# Schematic.net
KiCad netlist of a schematic drawn in Altium Designer
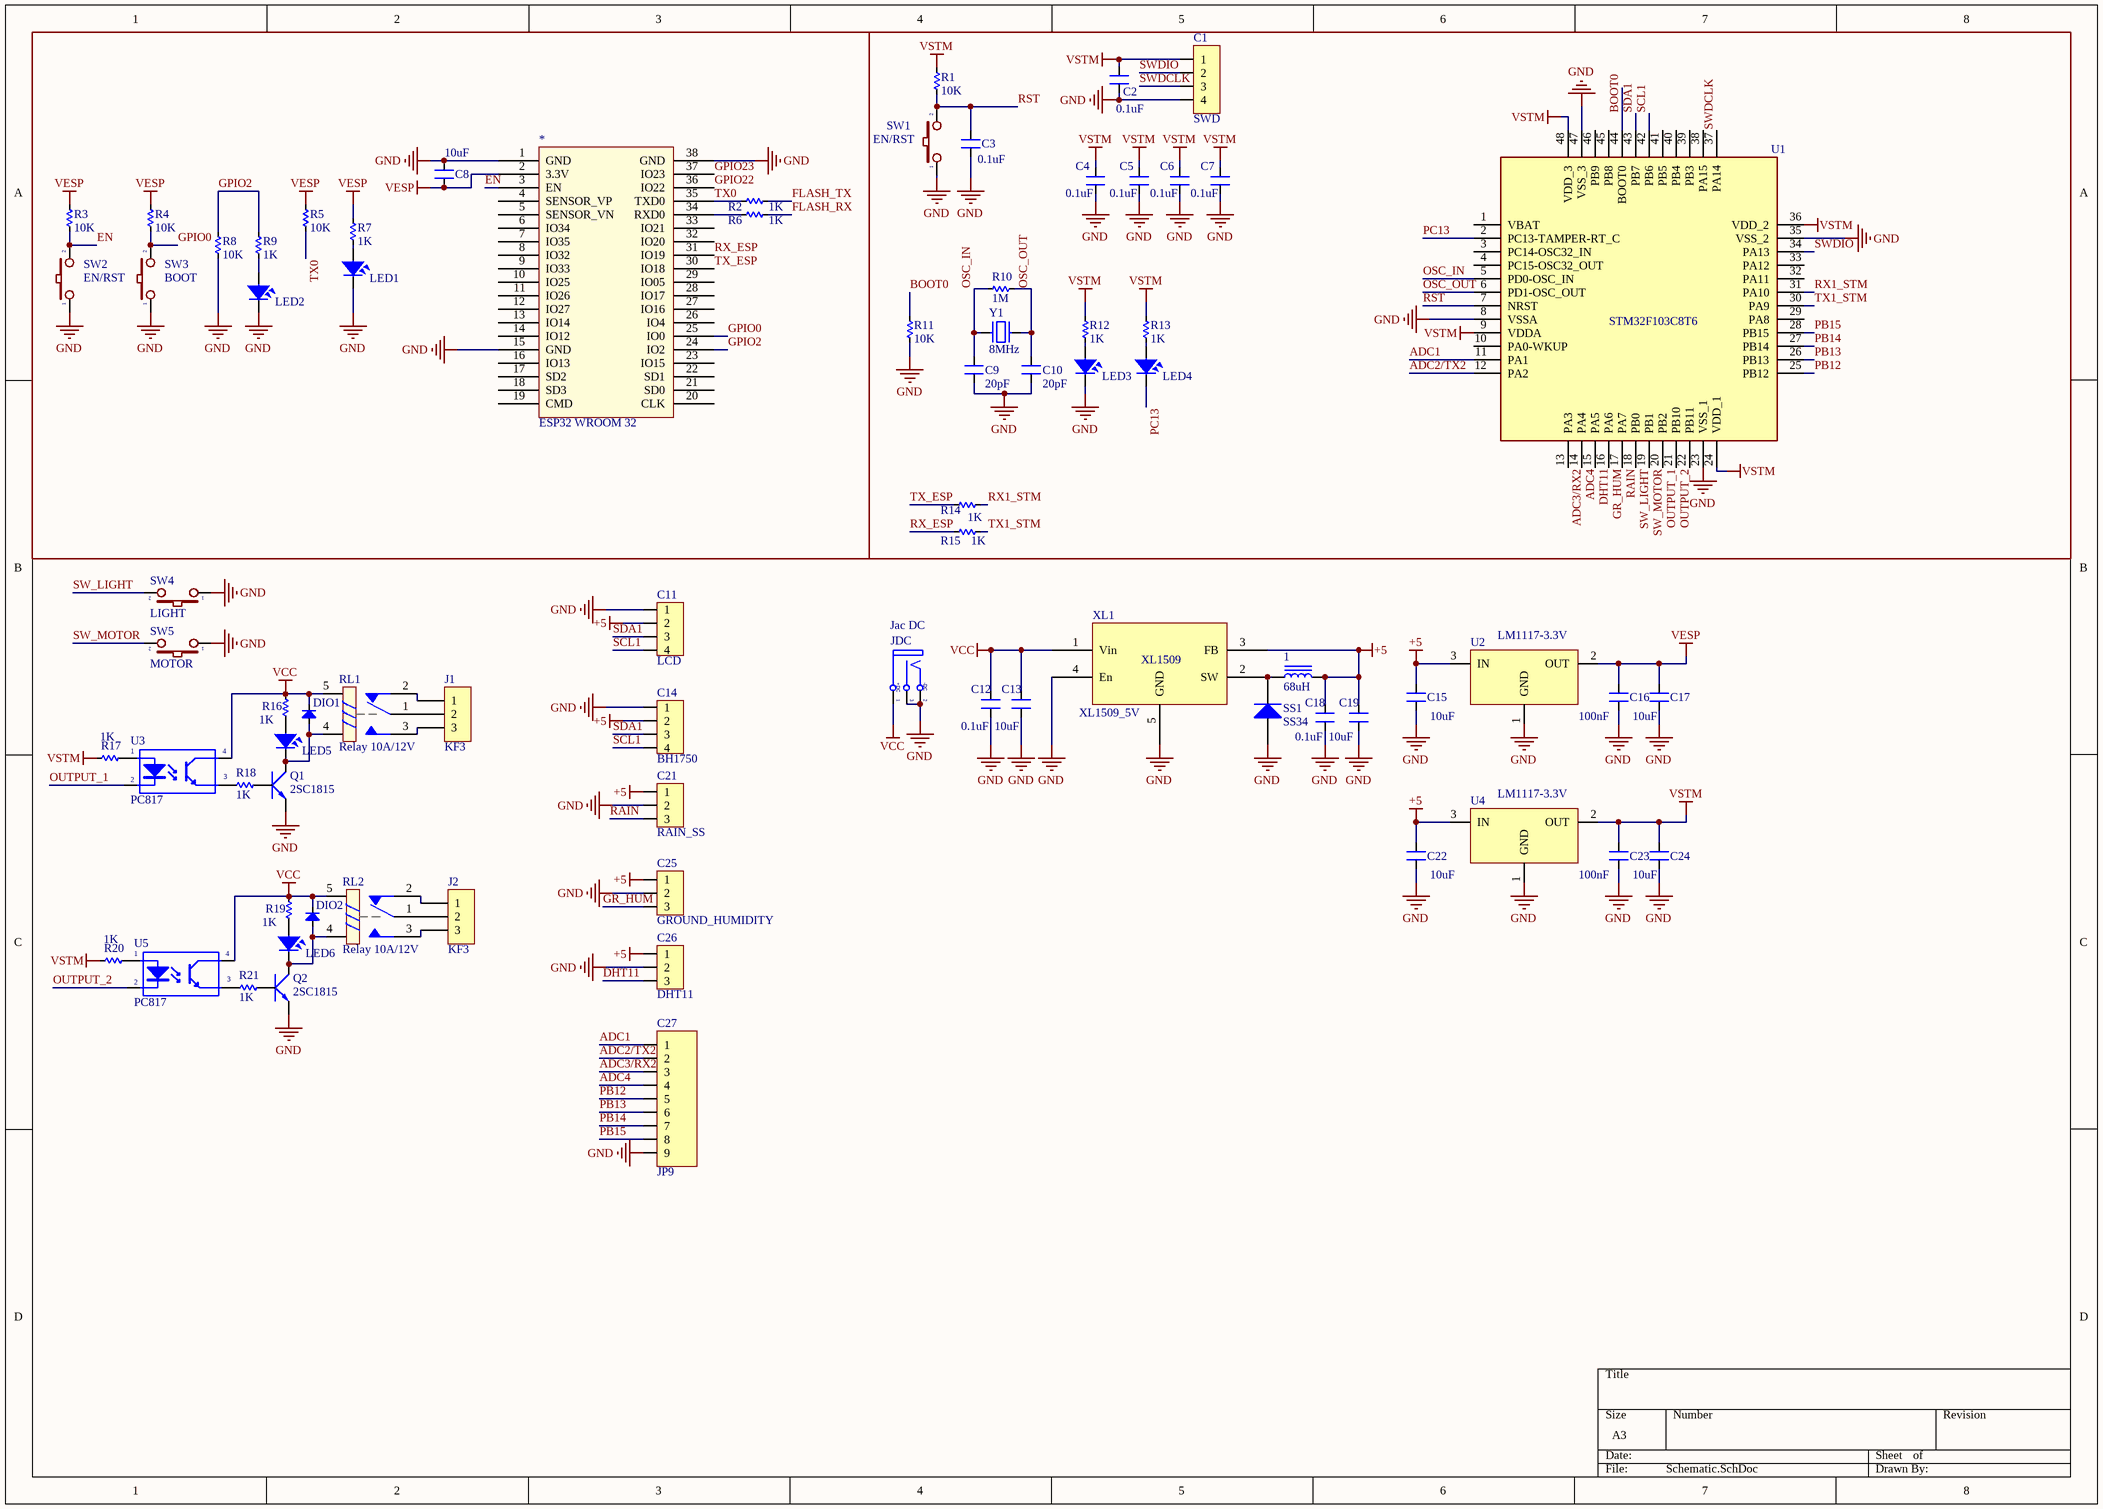
[diagram p0: Schematic.SchDoc]

(export (version "E")
  (design (tool "Eeschema 10.0.6"))
  (components
    (comp (ref "*")
      (value "ESP32 WROOM 32")
      (footprint "ESP32-WROOM-32D")
      (libsource (lib "Altium_Lib_by_KhueNguyenCreator") (part "ESP32 WROOM 32"))
    )
    (comp (ref "1")
      (value "68uH")
      (footprint "CDRH104R")
      (description "SMT Inductor")
      (libsource (lib "INDUCTOR") (part "Inductor"))
    )
    (comp (ref "C1")
      (value "SWD")
      (footprint "JP4-C1T")
      (description "WR-PHD 2.54 mm Angled Socket Header")
      (fields
        (field (name "MANUFACTURER") "Würth Elektronik eiSos GmbH")
        (field (name "PARTNO") "613004143121")
        (field (name "CREATED BY") "Karrer Zheng")
      )
      (libsource (lib "Library") (part "JP4"))
    )
    (comp (ref "C2")
      (value "0.1uF")
      (footprint "SM-0805")
      (description "Cap SMD")
      (libsource (lib "Capacitors") (part "CM"))
    )
    (comp (ref "C3")
      (value "0.1uF")
      (footprint "SM-0805")
      (description "Cap SMD")
      (libsource (lib "Capacitors") (part "CM"))
    )
    (comp (ref "C4")
      (value "0.1uF")
      (footprint "SM-0805")
      (description "Cap SMD")
      (libsource (lib "Capacitors") (part "CM"))
    )
    (comp (ref "C5")
      (value "0.1uF")
      (footprint "SM-0805")
      (description "Cap SMD")
      (libsource (lib "Capacitors") (part "CM"))
    )
    (comp (ref "C6")
      (value "0.1uF")
      (footprint "SM-0805")
      (description "Cap SMD")
      (libsource (lib "Capacitors") (part "CM"))
    )
    (comp (ref "C7")
      (value "0.1uF")
      (footprint "SM-0805")
      (description "Cap SMD")
      (libsource (lib "Capacitors") (part "CM"))
    )
    (comp (ref "C8")
      (value "10uF")
      (footprint "SM-0805")
      (description "Cap SMD")
      (libsource (lib "Capacitors") (part "CM"))
    )
    (comp (ref "C9")
      (value "20pF")
      (footprint "SM-0805")
      (description "Cap SMD")
      (libsource (lib "Capacitors") (part "CM"))
    )
    (comp (ref "C10")
      (value "20pF")
      (footprint "SM-0805")
      (description "Cap SMD")
      (libsource (lib "Capacitors") (part "CM"))
    )
    (comp (ref "C11")
      (value "LCD")
      (footprint "Header4")
      (description "Header IDC, 4 x 1 Pin Vertical 2.54mm Pitch (Non-Boxed, Male)")
      (fields
        (field (name "MANUFACTURER") "Würth Elektronik eiSos GmbH")
        (field (name "PARTNO") "613002143121")
        (field (name "CREATED BY") "Karrer Zheng")
      )
      (libsource (lib "Library") (part "Header4"))
    )
    (comp (ref "C12")
      (value "0.1uF")
      (footprint "SM-0805")
      (description "Cap SMD")
      (libsource (lib "Capacitors") (part "CM"))
    )
    (comp (ref "C13")
      (value "10uF")
      (footprint "SM-0805")
      (description "Cap SMD")
      (libsource (lib "Capacitors") (part "CM"))
    )
    (comp (ref "C14")
      (value "BH1750")
      (footprint "Header4")
      (description "Header IDC, 4 x 1 Pin Vertical 2.54mm Pitch (Non-Boxed, Male)")
      (fields
        (field (name "MANUFACTURER") "Würth Elektronik eiSos GmbH")
        (field (name "PARTNO") "613002143121")
        (field (name "CREATED BY") "Karrer Zheng")
      )
      (libsource (lib "Library") (part "Header4"))
    )
    (comp (ref "C15")
      (value "10uF")
      (footprint "SM-0805")
      (description "Cap SMD")
      (libsource (lib "Capacitors") (part "CM"))
    )
    (comp (ref "C16")
      (value "100nF")
      (footprint "SM-0805")
      (description "Cap SMD")
      (libsource (lib "Capacitors") (part "CM"))
    )
    (comp (ref "C17")
      (value "10uF")
      (footprint "SM-0805")
      (description "Cap SMD")
      (libsource (lib "Capacitors") (part "CM"))
    )
    (comp (ref "C18")
      (value "0.1uF")
      (footprint "SM-0805")
      (description "Cap SMD")
      (libsource (lib "Capacitors") (part "CM"))
    )
    (comp (ref "C19")
      (value "10uF")
      (footprint "SM-0805")
      (description "Cap SMD")
      (libsource (lib "Capacitors") (part "CM"))
    )
    (comp (ref "C21")
      (value "RAIN_SS")
      (footprint "Header3")
      (description "Header IDC, 3 x 1 Pin Vertical 2.54mm Pitch (Non-Boxed, Male)")
      (fields
        (field (name "MANUFACTURER") "Würth Elektronik eiSos GmbH")
        (field (name "PARTNO") "613002143121")
        (field (name "CREATED BY") "Karrer Zheng")
      )
      (libsource (lib "Library") (part "Header3"))
    )
    (comp (ref "C22")
      (value "10uF")
      (footprint "SM-0805")
      (description "Cap SMD")
      (libsource (lib "Capacitors") (part "CM"))
    )
    (comp (ref "C23")
      (value "100nF")
      (footprint "SM-0805")
      (description "Cap SMD")
      (libsource (lib "Capacitors") (part "CM"))
    )
    (comp (ref "C24")
      (value "10uF")
      (footprint "SM-0805")
      (description "Cap SMD")
      (libsource (lib "Capacitors") (part "CM"))
    )
    (comp (ref "C25")
      (value "GROUND_HUMIDITY")
      (footprint "Header3")
      (description "Header IDC, 3 x 1 Pin Vertical 2.54mm Pitch (Non-Boxed, Male)")
      (fields
        (field (name "MANUFACTURER") "Würth Elektronik eiSos GmbH")
        (field (name "PARTNO") "613002143121")
        (field (name "CREATED BY") "Karrer Zheng")
      )
      (libsource (lib "Library") (part "Header3"))
    )
    (comp (ref "C26")
      (value "DHT11")
      (footprint "Header3")
      (description "Header IDC, 3 x 1 Pin Vertical 2.54mm Pitch (Non-Boxed, Male)")
      (fields
        (field (name "MANUFACTURER") "Würth Elektronik eiSos GmbH")
        (field (name "PARTNO") "613002143121")
        (field (name "CREATED BY") "Karrer Zheng")
      )
      (libsource (lib "Library") (part "Header3"))
    )
    (comp (ref "C27")
      (value "JP9")
      (footprint "JP9-C1T")
      (description "WR-PHD 2.54 mm Angled Socket Header")
      (fields
        (field (name "MANUFACTURER") "Würth Elektronik eiSos GmbH")
        (field (name "PARTNO") "613009143121")
        (field (name "CREATED BY") "Karrer Zheng")
      )
      (libsource (lib "Library") (part "JP9"))
    )
    (comp (ref "DIO1")
      (value "Diode SMD")
      (footprint "DIO-SMD-A")
      (description "Default Diode")
      (fields (field (name "PUBLISHER") "Altium Limited"))
      (libsource (lib "Library") (part "Diode SMD"))
    )
    (comp (ref "DIO2")
      (value "Diode SMD")
      (footprint "DIO-SMD-A")
      (description "Default Diode")
      (fields (field (name "PUBLISHER") "Altium Limited"))
      (libsource (lib "Library") (part "Diode SMD"))
    )
    (comp (ref "J1")
      (value "KF3")
      (footprint "KF3_5.08_1")
      (fields
        (field (name "MANUFACTURER") "Würth Elektronik eiSos GmbH")
        (field (name "PARTNO") "691103110003")
        (field (name "CREATED BY") "Karrer Zheng")
      )
      (libsource (lib "Library") (part "KF3"))
    )
    (comp (ref "J2")
      (value "KF3")
      (footprint "KF3_5.08_1")
      (fields
        (field (name "MANUFACTURER") "Würth Elektronik eiSos GmbH")
        (field (name "PARTNO") "691103110003")
        (field (name "CREATED BY") "Karrer Zheng")
      )
      (libsource (lib "Library") (part "KF3"))
    )
    (comp (ref "JDC")
      (value "Jac DC")
      (footprint "DC0")
      (description "Jac DC input")
      (libsource (lib "Library") (part "DCIN"))
    )
    (comp (ref "LED1")
      (value "LED")
      (footprint "LED-0805-Green")
      (libsource (lib "Library") (part "LED SMD"))
    )
    (comp (ref "LED2")
      (value "LED")
      (footprint "LED-0805-Green")
      (libsource (lib "Library") (part "LED SMD"))
    )
    (comp (ref "LED3")
      (value "LED")
      (footprint "LED-0805-Green")
      (libsource (lib "Library") (part "LED SMD"))
    )
    (comp (ref "LED4")
      (value "LED")
      (footprint "LED-0805-Green")
      (libsource (lib "Library") (part "LED SMD"))
    )
    (comp (ref "LED5")
      (value "LED")
      (footprint "LED-0805-Green")
      (libsource (lib "Library") (part "LED SMD"))
    )
    (comp (ref "LED6")
      (value "LED")
      (footprint "LED-0805-Green")
      (libsource (lib "Library") (part "LED SMD"))
    )
    (comp (ref "Q1")
      (value "2SC1815")
      (footprint "SOT23-321")
      (description "NPN 600mW, ECB")
      (libsource (lib "Library") (part "2SC1815"))
    )
    (comp (ref "Q2")
      (value "2SC1815")
      (footprint "SOT23-321")
      (description "NPN 600mW, ECB")
      (libsource (lib "Library") (part "2SC1815"))
    )
    (comp (ref "R1")
      (value "10K")
      (footprint "RES-SMD-0805")
      (description "Resistor")
      (fields
        (field (name "MANUFACTURER") "Generic Components")
        (field (name "PUBLISHER") "Altium Hobart Technology Centre")
      )
      (libsource (lib "Library") (part "Res-SMD"))
    )
    (comp (ref "R2")
      (value "1K")
      (footprint "RES-SMD-0805")
      (description "Resistor")
      (fields
        (field (name "MANUFACTURER") "Generic Components")
        (field (name "PUBLISHER") "Altium Hobart Technology Centre")
      )
      (libsource (lib "Library") (part "Res-SMD"))
    )
    (comp (ref "R3")
      (value "10K")
      (footprint "RES-SMD-0805")
      (description "Resistor")
      (fields
        (field (name "MANUFACTURER") "Generic Components")
        (field (name "PUBLISHER") "Altium Hobart Technology Centre")
      )
      (libsource (lib "Library") (part "Res-SMD"))
    )
    (comp (ref "R4")
      (value "10K")
      (footprint "RES-SMD-0805")
      (description "Resistor")
      (fields
        (field (name "MANUFACTURER") "Generic Components")
        (field (name "PUBLISHER") "Altium Hobart Technology Centre")
      )
      (libsource (lib "Library") (part "Res-SMD"))
    )
    (comp (ref "R5")
      (value "10K")
      (footprint "RES-SMD-0805")
      (description "Resistor")
      (fields
        (field (name "MANUFACTURER") "Generic Components")
        (field (name "PUBLISHER") "Altium Hobart Technology Centre")
      )
      (libsource (lib "Library") (part "Res-SMD"))
    )
    (comp (ref "R6")
      (value "1K")
      (footprint "RES-SMD-0805")
      (description "Resistor")
      (fields
        (field (name "MANUFACTURER") "Generic Components")
        (field (name "PUBLISHER") "Altium Hobart Technology Centre")
      )
      (libsource (lib "Library") (part "Res-SMD"))
    )
    (comp (ref "R7")
      (value "1K")
      (footprint "RES-SMD-0805")
      (description "Resistor")
      (fields
        (field (name "MANUFACTURER") "Generic Components")
        (field (name "PUBLISHER") "Altium Hobart Technology Centre")
      )
      (libsource (lib "Library") (part "Res-SMD"))
    )
    (comp (ref "R8")
      (value "10K")
      (footprint "RES-SMD-0805")
      (description "Resistor")
      (fields
        (field (name "MANUFACTURER") "Generic Components")
        (field (name "PUBLISHER") "Altium Hobart Technology Centre")
      )
      (libsource (lib "Library") (part "Res-SMD"))
    )
    (comp (ref "R9")
      (value "1K")
      (footprint "RES-SMD-0805")
      (description "Resistor")
      (fields
        (field (name "MANUFACTURER") "Generic Components")
        (field (name "PUBLISHER") "Altium Hobart Technology Centre")
      )
      (libsource (lib "Library") (part "Res-SMD"))
    )
    (comp (ref "R10")
      (value "1M")
      (footprint "RES-SMD-0805")
      (description "Resistor")
      (fields
        (field (name "MANUFACTURER") "Generic Components")
        (field (name "PUBLISHER") "Altium Hobart Technology Centre")
      )
      (libsource (lib "Library") (part "Res-SMD"))
    )
    (comp (ref "R11")
      (value "10K")
      (footprint "RES-SMD-0805")
      (description "Resistor")
      (fields
        (field (name "MANUFACTURER") "Generic Components")
        (field (name "PUBLISHER") "Altium Hobart Technology Centre")
      )
      (libsource (lib "Library") (part "Res-SMD"))
    )
    (comp (ref "R12")
      (value "1K")
      (footprint "RES-SMD-0805")
      (description "Resistor")
      (fields
        (field (name "MANUFACTURER") "Generic Components")
        (field (name "PUBLISHER") "Altium Hobart Technology Centre")
      )
      (libsource (lib "Library") (part "Res-SMD"))
    )
    (comp (ref "R13")
      (value "1K")
      (footprint "RES-SMD-0805")
      (description "Resistor")
      (fields
        (field (name "MANUFACTURER") "Generic Components")
        (field (name "PUBLISHER") "Altium Hobart Technology Centre")
      )
      (libsource (lib "Library") (part "Res-SMD"))
    )
    (comp (ref "R14")
      (value "1K")
      (footprint "RES-SMD-0805")
      (description "Resistor")
      (fields
        (field (name "MANUFACTURER") "Generic Components")
        (field (name "PUBLISHER") "Altium Hobart Technology Centre")
      )
      (libsource (lib "Library") (part "Res-SMD"))
    )
    (comp (ref "R15")
      (value "1K")
      (footprint "RES-SMD-0805")
      (description "Resistor")
      (fields
        (field (name "MANUFACTURER") "Generic Components")
        (field (name "PUBLISHER") "Altium Hobart Technology Centre")
      )
      (libsource (lib "Library") (part "Res-SMD"))
    )
    (comp (ref "R16")
      (value "1K")
      (footprint "RES-SMD-0805")
      (description "Resistor")
      (fields
        (field (name "MANUFACTURER") "Generic Components")
        (field (name "PUBLISHER") "Altium Hobart Technology Centre")
      )
      (libsource (lib "Library") (part "Res-SMD"))
    )
    (comp (ref "R17")
      (value "1K")
      (footprint "RES-SMD-0805")
      (description "Resistor")
      (fields
        (field (name "MANUFACTURER") "Generic Components")
        (field (name "PUBLISHER") "Altium Hobart Technology Centre")
      )
      (libsource (lib "Library") (part "Res-SMD"))
    )
    (comp (ref "R18")
      (value "1K")
      (footprint "RES-SMD-0805")
      (description "Resistor")
      (fields
        (field (name "MANUFACTURER") "Generic Components")
        (field (name "PUBLISHER") "Altium Hobart Technology Centre")
      )
      (libsource (lib "Library") (part "Res-SMD"))
    )
    (comp (ref "R19")
      (value "1K")
      (footprint "RES-SMD-0805")
      (description "Resistor")
      (fields
        (field (name "MANUFACTURER") "Generic Components")
        (field (name "PUBLISHER") "Altium Hobart Technology Centre")
      )
      (libsource (lib "Library") (part "Res-SMD"))
    )
    (comp (ref "R20")
      (value "1K")
      (footprint "RES-SMD-0805")
      (description "Resistor")
      (fields
        (field (name "MANUFACTURER") "Generic Components")
        (field (name "PUBLISHER") "Altium Hobart Technology Centre")
      )
      (libsource (lib "Library") (part "Res-SMD"))
    )
    (comp (ref "R21")
      (value "1K")
      (footprint "RES-SMD-0805")
      (description "Resistor")
      (fields
        (field (name "MANUFACTURER") "Generic Components")
        (field (name "PUBLISHER") "Altium Hobart Technology Centre")
      )
      (libsource (lib "Library") (part "Res-SMD"))
    )
    (comp (ref "RL1")
      (value "Relay 10A/12V")
      (footprint "RELAY 5")
      (description "Relay SPDT,10A - 12VDC 5 Pin")
      (libsource (lib "Library") (part "Relay 5"))
    )
    (comp (ref "RL2")
      (value "Relay 10A/12V")
      (footprint "RELAY 5")
      (description "Relay SPDT,10A - 12VDC 5 Pin")
      (libsource (lib "Library") (part "Relay 5"))
    )
    (comp (ref "SS1")
      (value "SS34")
      (footprint "DIODE SMA")
      (description "Dán")
      (libsource (lib "Altium_Lib_by_KhueNguyenCreator") (part "Diode SS34 ( 1N5822 )"))
    )
    (comp (ref "SW1")
      (value "EN/RST")
      (footprint "SW1-SMD")
      (description "Switch button 2 pin")
      (libsource (lib "Library") (part "SW2"))
    )
    (comp (ref "SW2")
      (value "EN/RST")
      (footprint "SW1-SMD")
      (description "Switch button 2 pin")
      (libsource (lib "Library") (part "SW2"))
    )
    (comp (ref "SW3")
      (value "BOOT")
      (footprint "SW1-SMD")
      (description "Switch button 2 pin")
      (libsource (lib "Library") (part "SW2"))
    )
    (comp (ref "SW4")
      (value "LIGHT")
      (footprint "SW1-SMD")
      (description "Switch button 2 pin")
      (libsource (lib "Library") (part "SW2"))
    )
    (comp (ref "SW5")
      (value "MOTOR")
      (footprint "SW1-SMD")
      (description "Switch button 2 pin")
      (libsource (lib "Library") (part "SW2"))
    )
    (comp (ref "U1")
      (value "STM32F103C8T6")
      (footprint "LQFP-48_19.6_393_58X11_SMD")
      (description "ARM® Cortex®-M3 STM32F1 Microcontroller IC 32-Bit 72MHz 64KB (64K x 8) FLASH 48-LQFP (7x7)")
      (fields (field (name "MANUFACTURER") "STMicroelectronics"))
      (libsource (lib "Altium_Lib_by_KhueNguyenCreator") (part "IC_STM32F103C8T6"))
    )
    (comp (ref "U2")
      (value "LM1117-3.3V")
      (footprint "SOT223")
      (description "800mA Low-Dropout Linear Regulator")
      (fields (field (name "CREATOR") "Nguyen Ba Bien"))
      (libsource (lib "Library") (part "LM1117"))
    )
    (comp (ref "U3")
      (value "PC817")
      (footprint "PC817_SMD")
      (description "Single Opto")
      (libsource (lib "Library") (part "PC817"))
    )
    (comp (ref "U4")
      (value "LM1117-3.3V")
      (footprint "SOT223")
      (description "800mA Low-Dropout Linear Regulator")
      (fields (field (name "CREATOR") "Nguyen Ba Bien"))
      (libsource (lib "Library") (part "LM1117"))
    )
    (comp (ref "U5")
      (value "PC817")
      (footprint "PC817_SMD")
      (description "Single Opto")
      (libsource (lib "Library") (part "PC817"))
    )
    (comp (ref "XL1") (value "XL1509_5V") (footprint "SO8") (libsource (lib "Library") (part "XL1509")))
    (comp (ref "Y1")
      (value "8MHz")
      (footprint "Thach Anh 2 chan SMD")
      (description "Crystal For all Crystal 2pin.")
      (libsource (lib "Altium_Lib_by_KhueNguyenCreator") (part "Thach Anh 2 chan SMD"))
    )
  )
  (nets
    (net (code "1") (name "+5") (class "Default")
      (node (ref "1") (pin "2") (pinfunction "2_2") (pintype "passive"))
      (node (ref "C11") (pin "2") (pinfunction "2_2") (pintype "passive"))
      (node (ref "C14") (pin "2") (pinfunction "2_2") (pintype "passive"))
      (node (ref "C15") (pin "2") (pinfunction "2_2") (pintype "passive"))
      (node (ref "C18") (pin "1") (pinfunction "1_1") (pintype "passive"))
      (node (ref "C19") (pin "1") (pinfunction "1_1") (pintype "passive"))
      (node (ref "C21") (pin "1") (pinfunction "1_1") (pintype "passive"))
      (node (ref "C22") (pin "2") (pinfunction "2_2") (pintype "passive"))
      (node (ref "C25") (pin "1") (pinfunction "1_1") (pintype "passive"))
      (node (ref "C26") (pin "1") (pinfunction "1_1") (pintype "passive"))
      (node (ref "U2") (pin "3") (pinfunction "IN_3") (pintype "passive"))
      (node (ref "U4") (pin "3") (pinfunction "IN_3") (pintype "passive"))
      (node (ref "XL1") (pin "3") (pinfunction "FB_3") (pintype "passive"))
    )
    (net (code "2") (name "/ADC1") (class "Default")
      (node (ref "C27") (pin "1") (pinfunction "1_1") (pintype "passive"))
      (node (ref "U1") (pin "11") (pinfunction "PA1_11") (pintype "passive"))
    )
    (net (code "3") (name "/ADC2{slash}TX2") (class "Default")
      (node (ref "C27") (pin "2") (pinfunction "2_2") (pintype "passive"))
      (node (ref "U1") (pin "12") (pinfunction "PA2_12") (pintype "passive"))
    )
    (net (code "4") (name "/ADC3{slash}RX2") (class "Default")
      (node (ref "C27") (pin "3") (pinfunction "3_3") (pintype "passive"))
      (node (ref "U1") (pin "13") (pinfunction "PA3_13") (pintype "passive"))
    )
    (net (code "5") (name "/ADC4") (class "Default")
      (node (ref "C27") (pin "4") (pinfunction "4_4") (pintype "passive"))
      (node (ref "U1") (pin "14") (pinfunction "PA4_14") (pintype "passive"))
    )
    (net (code "6") (name "/BOOT0") (class "Default")
      (node (ref "R11") (pin "1") (pinfunction "1_1") (pintype "passive"))
      (node (ref "U1") (pin "44") (pinfunction "BOOT0_44") (pintype "passive"))
    )
    (net (code "7") (name "/DHT11") (class "Default")
      (node (ref "C26") (pin "3") (pinfunction "3_3") (pintype "passive"))
      (node (ref "U1") (pin "15") (pinfunction "PA5_15") (pintype "passive"))
    )
    (net (code "8") (name "/EN") (class "Default")
      (node (ref "*") (pin "3") (pinfunction "EN_3") (pintype "passive"))
      (node (ref "R3") (pin "2") (pinfunction "2_2") (pintype "passive"))
      (node (ref "SW2") (pin "2") (pinfunction "2_2") (pintype "passive"))
    )
    (net (code "9") (name "/FLASH_RX") (class "Default")
      (node (ref "R6") (pin "1") (pinfunction "1_1") (pintype "passive"))
    )
    (net (code "10") (name "/FLASH_TX") (class "Default")
      (node (ref "R2") (pin "1") (pinfunction "1_1") (pintype "passive"))
    )
    (net (code "11") (name "/GPIO0") (class "Default")
      (node (ref "*") (pin "25") (pinfunction "IO0_25") (pintype "passive"))
      (node (ref "R4") (pin "2") (pinfunction "2_2") (pintype "passive"))
      (node (ref "SW3") (pin "2") (pinfunction "2_2") (pintype "passive"))
    )
    (net (code "12") (name "/GPIO2") (class "Default")
      (node (ref "*") (pin "24") (pinfunction "IO2_24") (pintype "passive"))
      (node (ref "R8") (pin "1") (pinfunction "1_1") (pintype "passive"))
      (node (ref "R9") (pin "1") (pinfunction "1_1") (pintype "passive"))
    )
    (net (code "13") (name "/GPIO22") (class "Default")
      (node (ref "*") (pin "36") (pinfunction "IO22_36") (pintype "passive"))
    )
    (net (code "14") (name "/GPIO23") (class "Default")
      (node (ref "*") (pin "37") (pinfunction "IO23_37") (pintype "passive"))
    )
    (net (code "15") (name "/GR_HUM") (class "Default")
      (node (ref "C25") (pin "3") (pinfunction "3_3") (pintype "passive"))
      (node (ref "U1") (pin "16") (pinfunction "PA6_16") (pintype "passive"))
    )
    (net (code "16") (name "/OSC_IN") (class "Default")
      (node (ref "C9") (pin "1") (pinfunction "1_1") (pintype "passive"))
      (node (ref "R10") (pin "1") (pinfunction "1_1") (pintype "passive"))
      (node (ref "U1") (pin "5") (pinfunction "PD0-OSC_IN_5") (pintype "passive"))
      (node (ref "Y1") (pin "2") (pinfunction "2_2") (pintype "passive"))
    )
    (net (code "17") (name "/OSC_OUT") (class "Default")
      (node (ref "C10") (pin "1") (pinfunction "1_1") (pintype "passive"))
      (node (ref "R10") (pin "2") (pinfunction "2_2") (pintype "passive"))
      (node (ref "U1") (pin "6") (pinfunction "PD1-OSC_OUT_6") (pintype "passive"))
      (node (ref "Y1") (pin "1") (pinfunction "1_1") (pintype "passive"))
    )
    (net (code "18") (name "/OUTPUT_1") (class "Default")
      (node (ref "U1") (pin "20") (pinfunction "PB2_20") (pintype "passive"))
      (node (ref "U3") (pin "2") (pinfunction "K_2") (pintype "passive"))
    )
    (net (code "19") (name "/OUTPUT_2") (class "Default")
      (node (ref "U1") (pin "21") (pinfunction "PB10_21") (pintype "passive"))
      (node (ref "U5") (pin "2") (pinfunction "K_2") (pintype "passive"))
    )
    (net (code "20") (name "/PB12") (class "Default")
      (node (ref "C27") (pin "5") (pinfunction "5_5") (pintype "passive"))
      (node (ref "U1") (pin "25") (pinfunction "PB12_25") (pintype "passive"))
    )
    (net (code "21") (name "/PB13") (class "Default")
      (node (ref "C27") (pin "6") (pinfunction "6_6") (pintype "passive"))
      (node (ref "U1") (pin "26") (pinfunction "PB13_26") (pintype "passive"))
    )
    (net (code "22") (name "/PB14") (class "Default")
      (node (ref "C27") (pin "7") (pinfunction "7_7") (pintype "passive"))
      (node (ref "U1") (pin "27") (pinfunction "PB14_27") (pintype "passive"))
    )
    (net (code "23") (name "/PB15") (class "Default")
      (node (ref "C27") (pin "8") (pinfunction "8_8") (pintype "passive"))
      (node (ref "U1") (pin "28") (pinfunction "PB15_28") (pintype "passive"))
    )
    (net (code "24") (name "/PC13") (class "Default")
      (node (ref "LED4") (pin "2") (pinfunction "2_2") (pintype "passive"))
      (node (ref "U1") (pin "2") (pinfunction "PC13-TAMPER-RT_C_2") (pintype "passive"))
    )
    (net (code "25") (name "/RAIN") (class "Default")
      (node (ref "C21") (pin "3") (pinfunction "3_3") (pintype "passive"))
      (node (ref "U1") (pin "17") (pinfunction "PA7_17") (pintype "passive"))
    )
    (net (code "26") (name "/RST") (class "Default")
      (node (ref "C3") (pin "2") (pinfunction "2_2") (pintype "passive"))
      (node (ref "R1") (pin "2") (pinfunction "2_2") (pintype "passive"))
      (node (ref "SW1") (pin "2") (pinfunction "2_2") (pintype "passive"))
      (node (ref "U1") (pin "7") (pinfunction "NRST_7") (pintype "passive"))
    )
    (net (code "27") (name "/RX1_STM") (class "Default")
      (node (ref "R14") (pin "2") (pinfunction "2_2") (pintype "passive"))
      (node (ref "U1") (pin "31") (pinfunction "PA10_31") (pintype "passive"))
    )
    (net (code "28") (name "/RX_ESP") (class "Default")
      (node (ref "*") (pin "31") (pinfunction "IO19_31") (pintype "passive"))
      (node (ref "R15") (pin "1") (pinfunction "1_1") (pintype "passive"))
    )
    (net (code "29") (name "/SCL1") (class "Default")
      (node (ref "C11") (pin "4") (pinfunction "4_4") (pintype "passive"))
      (node (ref "C14") (pin "4") (pinfunction "4_4") (pintype "passive"))
      (node (ref "U1") (pin "42") (pinfunction "PB6_42") (pintype "passive"))
    )
    (net (code "30") (name "/SDA1") (class "Default")
      (node (ref "C11") (pin "3") (pinfunction "3_3") (pintype "passive"))
      (node (ref "C14") (pin "3") (pinfunction "3_3") (pintype "passive"))
      (node (ref "U1") (pin "43") (pinfunction "PB7_43") (pintype "passive"))
    )
    (net (code "31") (name "/SWDCLK") (class "Default")
      (node (ref "C1") (pin "3") (pinfunction "3_3") (pintype "passive"))
      (node (ref "U1") (pin "37") (pinfunction "PA14_37") (pintype "passive"))
    )
    (net (code "32") (name "/SWDIO") (class "Default")
      (node (ref "C1") (pin "2") (pinfunction "2_2") (pintype "passive"))
      (node (ref "U1") (pin "34") (pinfunction "PA13_34") (pintype "passive"))
    )
    (net (code "33") (name "/SW_LIGHT") (class "Default")
      (node (ref "SW4") (pin "2") (pinfunction "2_2") (pintype "passive"))
      (node (ref "U1") (pin "18") (pinfunction "PB0_18") (pintype "passive"))
    )
    (net (code "34") (name "/SW_MOTOR") (class "Default")
      (node (ref "SW5") (pin "2") (pinfunction "2_2") (pintype "passive"))
      (node (ref "U1") (pin "19") (pinfunction "PB1_19") (pintype "passive"))
    )
    (net (code "35") (name "/TX0") (class "Default")
      (node (ref "*") (pin "35") (pinfunction "TXD0_35") (pintype "passive"))
      (node (ref "R2") (pin "2") (pinfunction "2_2") (pintype "passive"))
      (node (ref "R5") (pin "2") (pinfunction "2_2") (pintype "passive"))
    )
    (net (code "36") (name "/TX1_STM") (class "Default")
      (node (ref "R15") (pin "2") (pinfunction "2_2") (pintype "passive"))
      (node (ref "U1") (pin "30") (pinfunction "PA9_30") (pintype "passive"))
    )
    (net (code "37") (name "/TX_ESP") (class "Default")
      (node (ref "*") (pin "30") (pinfunction "IO18_30") (pintype "passive"))
      (node (ref "R14") (pin "1") (pinfunction "1_1") (pintype "passive"))
    )
    (net (code "38") (name "GND") (class "Default")
      (node (ref "*") (pin "1") (pinfunction "GND_1") (pintype "passive"))
      (node (ref "*") (pin "15") (pinfunction "GND_15") (pintype "passive"))
      (node (ref "*") (pin "38") (pinfunction "GND_38") (pintype "passive"))
      (node (ref "C1") (pin "4") (pinfunction "4_4") (pintype "passive"))
      (node (ref "C10") (pin "2") (pinfunction "2_2") (pintype "passive"))
      (node (ref "C11") (pin "1") (pinfunction "1_1") (pintype "passive"))
      (node (ref "C12") (pin "2") (pinfunction "2_2") (pintype "passive"))
      (node (ref "C13") (pin "2") (pinfunction "2_2") (pintype "passive"))
      (node (ref "C14") (pin "1") (pinfunction "1_1") (pintype "passive"))
      (node (ref "C15") (pin "1") (pinfunction "1_1") (pintype "passive"))
      (node (ref "C16") (pin "1") (pinfunction "1_1") (pintype "passive"))
      (node (ref "C17") (pin "1") (pinfunction "1_1") (pintype "passive"))
      (node (ref "C18") (pin "2") (pinfunction "2_2") (pintype "passive"))
      (node (ref "C19") (pin "2") (pinfunction "2_2") (pintype "passive"))
      (node (ref "C2") (pin "2") (pinfunction "2_2") (pintype "passive"))
      (node (ref "C21") (pin "2") (pinfunction "2_2") (pintype "passive"))
      (node (ref "C22") (pin "1") (pinfunction "1_1") (pintype "passive"))
      (node (ref "C23") (pin "1") (pinfunction "1_1") (pintype "passive"))
      (node (ref "C24") (pin "1") (pinfunction "1_1") (pintype "passive"))
      (node (ref "C25") (pin "2") (pinfunction "2_2") (pintype "passive"))
      (node (ref "C26") (pin "2") (pinfunction "2_2") (pintype "passive"))
      (node (ref "C27") (pin "9") (pinfunction "9_9") (pintype "passive"))
      (node (ref "C3") (pin "1") (pinfunction "1_1") (pintype "passive"))
      (node (ref "C4") (pin "2") (pinfunction "2_2") (pintype "passive"))
      (node (ref "C5") (pin "2") (pinfunction "2_2") (pintype "passive"))
      (node (ref "C6") (pin "2") (pinfunction "2_2") (pintype "passive"))
      (node (ref "C7") (pin "2") (pinfunction "2_2") (pintype "passive"))
      (node (ref "C8") (pin "2") (pinfunction "2_2") (pintype "passive"))
      (node (ref "C9") (pin "2") (pinfunction "2_2") (pintype "passive"))
      (node (ref "JDC") (pin "2") (pinfunction "TN_2") (pintype "passive"))
      (node (ref "JDC") (pin "3") (pinfunction "S_3") (pintype "power_in"))
      (node (ref "LED1") (pin "2") (pinfunction "2_2") (pintype "passive"))
      (node (ref "LED2") (pin "2") (pinfunction "2_2") (pintype "passive"))
      (node (ref "LED3") (pin "2") (pinfunction "2_2") (pintype "passive"))
      (node (ref "Q1") (pin "1") (pinfunction "E_1") (pintype "passive"))
      (node (ref "Q2") (pin "1") (pinfunction "E_1") (pintype "passive"))
      (node (ref "R11") (pin "2") (pinfunction "2_2") (pintype "passive"))
      (node (ref "R8") (pin "2") (pinfunction "2_2") (pintype "passive"))
      (node (ref "SS1") (pin "1") (pinfunction "A_1") (pintype "passive"))
      (node (ref "SW1") (pin "1") (pinfunction "1_1") (pintype "passive"))
      (node (ref "SW2") (pin "1") (pinfunction "1_1") (pintype "passive"))
      (node (ref "SW3") (pin "1") (pinfunction "1_1") (pintype "passive"))
      (node (ref "SW4") (pin "1") (pinfunction "1_1") (pintype "passive"))
      (node (ref "SW5") (pin "1") (pinfunction "1_1") (pintype "passive"))
      (node (ref "U1") (pin "23") (pinfunction "VSS_1_23") (pintype "passive"))
      (node (ref "U1") (pin "35") (pinfunction "VSS_2_35") (pintype "passive"))
      (node (ref "U1") (pin "47") (pinfunction "VSS_3_47") (pintype "passive"))
      (node (ref "U1") (pin "8") (pinfunction "VSSA_8") (pintype "passive"))
      (node (ref "U2") (pin "1") (pinfunction "GND_1") (pintype "passive"))
      (node (ref "U4") (pin "1") (pinfunction "GND_1") (pintype "passive"))
      (node (ref "XL1") (pin "4") (pinfunction "En_4") (pintype "passive"))
      (node (ref "XL1") (pin "5") (pinfunction "GND_5") (pintype "passive"))
    )
    (net (code "39") (name "Net-(*-RXD0)") (class "Default")
      (node (ref "*") (pin "34") (pinfunction "RXD0_34") (pintype "passive"))
      (node (ref "R6") (pin "2") (pinfunction "2_2") (pintype "passive"))
    )
    (net (code "40") (name "Net-(DIO1-A)") (class "Default")
      (node (ref "DIO1") (pin "1") (pinfunction "A_1") (pintype "passive"))
      (node (ref "LED5") (pin "2") (pinfunction "2_2") (pintype "passive"))
      (node (ref "Q1") (pin "2") (pinfunction "C_2") (pintype "passive"))
      (node (ref "RL1") (pin "4") (pinfunction "4_4") (pintype "passive"))
    )
    (net (code "41") (name "Net-(DIO2-A)") (class "Default")
      (node (ref "DIO2") (pin "1") (pinfunction "A_1") (pintype "passive"))
      (node (ref "LED6") (pin "2") (pinfunction "2_2") (pintype "passive"))
      (node (ref "Q2") (pin "2") (pinfunction "C_2") (pintype "passive"))
      (node (ref "RL2") (pin "4") (pinfunction "4_4") (pintype "passive"))
    )
    (net (code "42") (name "Net-(J1-Pad1)") (class "Default")
      (node (ref "J1") (pin "1") (pinfunction "1_1") (pintype "passive"))
      (node (ref "RL1") (pin "2") (pinfunction "2_2") (pintype "passive"))
    )
    (net (code "43") (name "Net-(J1-Pad2)") (class "Default")
      (node (ref "J1") (pin "2") (pinfunction "2_2") (pintype "passive"))
      (node (ref "RL1") (pin "1") (pinfunction "1_1") (pintype "passive"))
    )
    (net (code "44") (name "Net-(J1-Pad3)") (class "Default")
      (node (ref "J1") (pin "3") (pinfunction "3_3") (pintype "passive"))
      (node (ref "RL1") (pin "3") (pinfunction "3_3") (pintype "passive"))
    )
    (net (code "45") (name "Net-(J2-Pad1)") (class "Default")
      (node (ref "J2") (pin "1") (pinfunction "1_1") (pintype "passive"))
      (node (ref "RL2") (pin "2") (pinfunction "2_2") (pintype "passive"))
    )
    (net (code "46") (name "Net-(J2-Pad2)") (class "Default")
      (node (ref "J2") (pin "2") (pinfunction "2_2") (pintype "passive"))
      (node (ref "RL2") (pin "1") (pinfunction "1_1") (pintype "passive"))
    )
    (net (code "47") (name "Net-(J2-Pad3)") (class "Default")
      (node (ref "J2") (pin "3") (pinfunction "3_3") (pintype "passive"))
      (node (ref "RL2") (pin "3") (pinfunction "3_3") (pintype "passive"))
    )
    (net (code "48") (name "Net-(LED1-Pad1)") (class "Default")
      (node (ref "LED1") (pin "1") (pinfunction "1_1") (pintype "passive"))
      (node (ref "R7") (pin "2") (pinfunction "2_2") (pintype "passive"))
    )
    (net (code "49") (name "Net-(LED2-Pad1)") (class "Default")
      (node (ref "LED2") (pin "1") (pinfunction "1_1") (pintype "passive"))
      (node (ref "R9") (pin "2") (pinfunction "2_2") (pintype "passive"))
    )
    (net (code "50") (name "Net-(LED3-Pad1)") (class "Default")
      (node (ref "LED3") (pin "1") (pinfunction "1_1") (pintype "passive"))
      (node (ref "R12") (pin "2") (pinfunction "2_2") (pintype "passive"))
    )
    (net (code "51") (name "Net-(LED4-Pad1)") (class "Default")
      (node (ref "LED4") (pin "1") (pinfunction "1_1") (pintype "passive"))
      (node (ref "R13") (pin "2") (pinfunction "2_2") (pintype "passive"))
    )
    (net (code "52") (name "Net-(LED5-Pad1)") (class "Default")
      (node (ref "LED5") (pin "1") (pinfunction "1_1") (pintype "passive"))
      (node (ref "R16") (pin "2") (pinfunction "2_2") (pintype "passive"))
    )
    (net (code "53") (name "Net-(LED6-Pad1)") (class "Default")
      (node (ref "LED6") (pin "1") (pinfunction "1_1") (pintype "passive"))
      (node (ref "R19") (pin "2") (pinfunction "2_2") (pintype "passive"))
    )
    (net (code "54") (name "Net-(Q1-B)") (class "Default")
      (node (ref "Q1") (pin "3") (pinfunction "B_3") (pintype "passive"))
      (node (ref "R18") (pin "2") (pinfunction "2_2") (pintype "passive"))
    )
    (net (code "55") (name "Net-(Q2-B)") (class "Default")
      (node (ref "Q2") (pin "3") (pinfunction "B_3") (pintype "passive"))
      (node (ref "R21") (pin "2") (pinfunction "2_2") (pintype "passive"))
    )
    (net (code "56") (name "Net-(SS1-K)") (class "Default")
      (node (ref "1") (pin "1") (pinfunction "1_1") (pintype "passive"))
      (node (ref "SS1") (pin "2") (pinfunction "K_2") (pintype "passive"))
      (node (ref "XL1") (pin "2") (pinfunction "SW_2") (pintype "passive"))
    )
    (net (code "57") (name "Net-(U3-A)") (class "Default")
      (node (ref "R17") (pin "1") (pinfunction "1_1") (pintype "passive"))
      (node (ref "U3") (pin "1") (pinfunction "A_1") (pintype "passive"))
    )
    (net (code "58") (name "Net-(U3-E)") (class "Default")
      (node (ref "R18") (pin "1") (pinfunction "1_1") (pintype "passive"))
      (node (ref "U3") (pin "3") (pinfunction "E_3") (pintype "passive"))
    )
    (net (code "59") (name "Net-(U5-A)") (class "Default")
      (node (ref "R20") (pin "1") (pinfunction "1_1") (pintype "passive"))
      (node (ref "U5") (pin "1") (pinfunction "A_1") (pintype "passive"))
    )
    (net (code "60") (name "Net-(U5-E)") (class "Default")
      (node (ref "R21") (pin "1") (pinfunction "1_1") (pintype "passive"))
      (node (ref "U5") (pin "3") (pinfunction "E_3") (pintype "passive"))
    )
    (net (code "61") (name "VCC") (class "Default")
      (node (ref "C12") (pin "1") (pinfunction "1_1") (pintype "passive"))
      (node (ref "C13") (pin "1") (pinfunction "1_1") (pintype "passive"))
      (node (ref "DIO1") (pin "2") (pinfunction "K_2") (pintype "passive"))
      (node (ref "DIO2") (pin "2") (pinfunction "K_2") (pintype "passive"))
      (node (ref "JDC") (pin "1") (pinfunction "T_1") (pintype "passive"))
      (node (ref "R16") (pin "1") (pinfunction "1_1") (pintype "passive"))
      (node (ref "R19") (pin "1") (pinfunction "1_1") (pintype "passive"))
      (node (ref "RL1") (pin "5") (pinfunction "5_5") (pintype "passive"))
      (node (ref "RL2") (pin "5") (pinfunction "5_5") (pintype "passive"))
      (node (ref "U3") (pin "4") (pinfunction "C_4") (pintype "passive"))
      (node (ref "U5") (pin "4") (pinfunction "C_4") (pintype "passive"))
      (node (ref "XL1") (pin "1") (pinfunction "Vin_1") (pintype "passive"))
    )
    (net (code "62") (name "VESP") (class "Default")
      (node (ref "*") (pin "2") (pinfunction "3.3V_2") (pintype "passive"))
      (node (ref "C16") (pin "2") (pinfunction "2_2") (pintype "passive"))
      (node (ref "C17") (pin "2") (pinfunction "2_2") (pintype "passive"))
      (node (ref "C8") (pin "1") (pinfunction "1_1") (pintype "passive"))
      (node (ref "R3") (pin "1") (pinfunction "1_1") (pintype "passive"))
      (node (ref "R4") (pin "1") (pinfunction "1_1") (pintype "passive"))
      (node (ref "R5") (pin "1") (pinfunction "1_1") (pintype "passive"))
      (node (ref "R7") (pin "1") (pinfunction "1_1") (pintype "passive"))
      (node (ref "U2") (pin "2") (pinfunction "OUT_2") (pintype "passive"))
    )
    (net (code "63") (name "VSTM") (class "Default")
      (node (ref "C1") (pin "1") (pinfunction "1_1") (pintype "passive"))
      (node (ref "C2") (pin "1") (pinfunction "1_1") (pintype "passive"))
      (node (ref "C23") (pin "2") (pinfunction "2_2") (pintype "passive"))
      (node (ref "C24") (pin "2") (pinfunction "2_2") (pintype "passive"))
      (node (ref "C4") (pin "1") (pinfunction "1_1") (pintype "passive"))
      (node (ref "C5") (pin "1") (pinfunction "1_1") (pintype "passive"))
      (node (ref "C6") (pin "1") (pinfunction "1_1") (pintype "passive"))
      (node (ref "C7") (pin "1") (pinfunction "1_1") (pintype "passive"))
      (node (ref "R1") (pin "1") (pinfunction "1_1") (pintype "passive"))
      (node (ref "R12") (pin "1") (pinfunction "1_1") (pintype "passive"))
      (node (ref "R13") (pin "1") (pinfunction "1_1") (pintype "passive"))
      (node (ref "R17") (pin "2") (pinfunction "2_2") (pintype "passive"))
      (node (ref "R20") (pin "2") (pinfunction "2_2") (pintype "passive"))
      (node (ref "U1") (pin "24") (pinfunction "VDD_1_24") (pintype "passive"))
      (node (ref "U1") (pin "36") (pinfunction "VDD_2_36") (pintype "passive"))
      (node (ref "U1") (pin "48") (pinfunction "VDD_3_48") (pintype "passive"))
      (node (ref "U1") (pin "9") (pinfunction "VDDA_9") (pintype "passive"))
      (node (ref "U4") (pin "2") (pinfunction "OUT_2") (pintype "passive"))
    )
    (net (code "64") (name "unconnected-(*-CLK-Pad20)") (class "Default")
      (node (ref "*") (pin "20") (pinfunction "CLK_20") (pintype "passive"))
    )
    (net (code "65") (name "unconnected-(*-CMD-Pad19)") (class "Default")
      (node (ref "*") (pin "19") (pinfunction "CMD_19") (pintype "passive"))
    )
    (net (code "66") (name "unconnected-(*-IO4-Pad26)") (class "Default")
      (node (ref "*") (pin "26") (pinfunction "IO4_26") (pintype "passive"))
    )
    (net (code "67") (name "unconnected-(*-IO05-Pad29)") (class "Default")
      (node (ref "*") (pin "29") (pinfunction "IO05_29") (pintype "passive"))
    )
    (net (code "68") (name "unconnected-(*-IO12-Pad14)") (class "Default")
      (node (ref "*") (pin "14") (pinfunction "IO12_14") (pintype "passive"))
    )
    (net (code "69") (name "unconnected-(*-IO13-Pad16)") (class "Default")
      (node (ref "*") (pin "16") (pinfunction "IO13_16") (pintype "passive"))
    )
    (net (code "70") (name "unconnected-(*-IO14-Pad13)") (class "Default")
      (node (ref "*") (pin "13") (pinfunction "IO14_13") (pintype "passive"))
    )
    (net (code "71") (name "unconnected-(*-IO15-Pad23)") (class "Default")
      (node (ref "*") (pin "23") (pinfunction "IO15_23") (pintype "passive"))
    )
    (net (code "72") (name "unconnected-(*-IO16-Pad27)") (class "Default")
      (node (ref "*") (pin "27") (pinfunction "IO16_27") (pintype "passive"))
    )
    (net (code "73") (name "unconnected-(*-IO17-Pad28)") (class "Default")
      (node (ref "*") (pin "28") (pinfunction "IO17_28") (pintype "passive"))
    )
    (net (code "74") (name "unconnected-(*-IO20-Pad32)") (class "Default")
      (node (ref "*") (pin "32") (pinfunction "IO20_32") (pintype "passive"))
    )
    (net (code "75") (name "unconnected-(*-IO21-Pad33)") (class "Default")
      (node (ref "*") (pin "33") (pinfunction "IO21_33") (pintype "passive"))
    )
    (net (code "76") (name "unconnected-(*-IO25-Pad10)") (class "Default")
      (node (ref "*") (pin "10") (pinfunction "IO25_10") (pintype "passive"))
    )
    (net (code "77") (name "unconnected-(*-IO26-Pad11)") (class "Default")
      (node (ref "*") (pin "11") (pinfunction "IO26_11") (pintype "passive"))
    )
    (net (code "78") (name "unconnected-(*-IO27-Pad12)") (class "Default")
      (node (ref "*") (pin "12") (pinfunction "IO27_12") (pintype "passive"))
    )
    (net (code "79") (name "unconnected-(*-IO32-Pad8)") (class "Default")
      (node (ref "*") (pin "8") (pinfunction "IO32_8") (pintype "passive"))
    )
    (net (code "80") (name "unconnected-(*-IO33-Pad9)") (class "Default")
      (node (ref "*") (pin "9") (pinfunction "IO33_9") (pintype "passive"))
    )
    (net (code "81") (name "unconnected-(*-IO34-Pad6)") (class "Default")
      (node (ref "*") (pin "6") (pinfunction "IO34_6") (pintype "passive"))
    )
    (net (code "82") (name "unconnected-(*-IO35-Pad7)") (class "Default")
      (node (ref "*") (pin "7") (pinfunction "IO35_7") (pintype "passive"))
    )
    (net (code "83") (name "unconnected-(*-SD0-Pad21)") (class "Default")
      (node (ref "*") (pin "21") (pinfunction "SD0_21") (pintype "passive"))
    )
    (net (code "84") (name "unconnected-(*-SD1-Pad22)") (class "Default")
      (node (ref "*") (pin "22") (pinfunction "SD1_22") (pintype "passive"))
    )
    (net (code "85") (name "unconnected-(*-SD2-Pad17)") (class "Default")
      (node (ref "*") (pin "17") (pinfunction "SD2_17") (pintype "passive"))
    )
    (net (code "86") (name "unconnected-(*-SD3-Pad18)") (class "Default")
      (node (ref "*") (pin "18") (pinfunction "SD3_18") (pintype "passive"))
    )
    (net (code "87") (name "unconnected-(*-SENSOR_VN-Pad5)") (class "Default")
      (node (ref "*") (pin "5") (pinfunction "SENSOR_VN_5") (pintype "passive"))
    )
    (net (code "88") (name "unconnected-(*-SENSOR_VP-Pad4)") (class "Default")
      (node (ref "*") (pin "4") (pinfunction "SENSOR_VP_4") (pintype "passive"))
    )
    (net (code "89") (name "unconnected-(U1-PA0-WKUP-Pad10)") (class "Default")
      (node (ref "U1") (pin "10") (pinfunction "PA0-WKUP_10") (pintype "passive"))
    )
    (net (code "90") (name "unconnected-(U1-PA8-Pad29)") (class "Default")
      (node (ref "U1") (pin "29") (pinfunction "PA8_29") (pintype "passive"))
    )
    (net (code "91") (name "unconnected-(U1-PA11-Pad32)") (class "Default")
      (node (ref "U1") (pin "32") (pinfunction "PA11_32") (pintype "passive"))
    )
    (net (code "92") (name "unconnected-(U1-PA12-Pad33)") (class "Default")
      (node (ref "U1") (pin "33") (pinfunction "PA12_33") (pintype "passive"))
    )
    (net (code "93") (name "unconnected-(U1-PA15-Pad38)") (class "Default")
      (node (ref "U1") (pin "38") (pinfunction "PA15_38") (pintype "passive"))
    )
    (net (code "94") (name "unconnected-(U1-PB3-Pad39)") (class "Default")
      (node (ref "U1") (pin "39") (pinfunction "PB3_39") (pintype "passive"))
    )
    (net (code "95") (name "unconnected-(U1-PB4-Pad40)") (class "Default")
      (node (ref "U1") (pin "40") (pinfunction "PB4_40") (pintype "passive"))
    )
    (net (code "96") (name "unconnected-(U1-PB5-Pad41)") (class "Default")
      (node (ref "U1") (pin "41") (pinfunction "PB5_41") (pintype "passive"))
    )
    (net (code "97") (name "unconnected-(U1-PB8-Pad45)") (class "Default")
      (node (ref "U1") (pin "45") (pinfunction "PB8_45") (pintype "passive"))
    )
    (net (code "98") (name "unconnected-(U1-PB9-Pad46)") (class "Default")
      (node (ref "U1") (pin "46") (pinfunction "PB9_46") (pintype "passive"))
    )
    (net (code "99") (name "unconnected-(U1-PB11-Pad22)") (class "Default")
      (node (ref "U1") (pin "22") (pinfunction "PB11_22") (pintype "passive"))
    )
    (net (code "100") (name "unconnected-(U1-PC14-OSC32_IN-Pad3)") (class "Default")
      (node (ref "U1") (pin "3") (pinfunction "PC14-OSC32_IN_3") (pintype "passive"))
    )
    (net (code "101") (name "unconnected-(U1-PC15-OSC32_OUT-Pad4)") (class "Default")
      (node (ref "U1") (pin "4") (pinfunction "PC15-OSC32_OUT_4") (pintype "passive"))
    )
    (net (code "102") (name "unconnected-(U1-VBAT-Pad1)") (class "Default")
      (node (ref "U1") (pin "1") (pinfunction "VBAT_1") (pintype "passive"))
    )
  )
)
